# Covox_backplate.net
KiCad netlist of a schematic drawn in EasyEDA
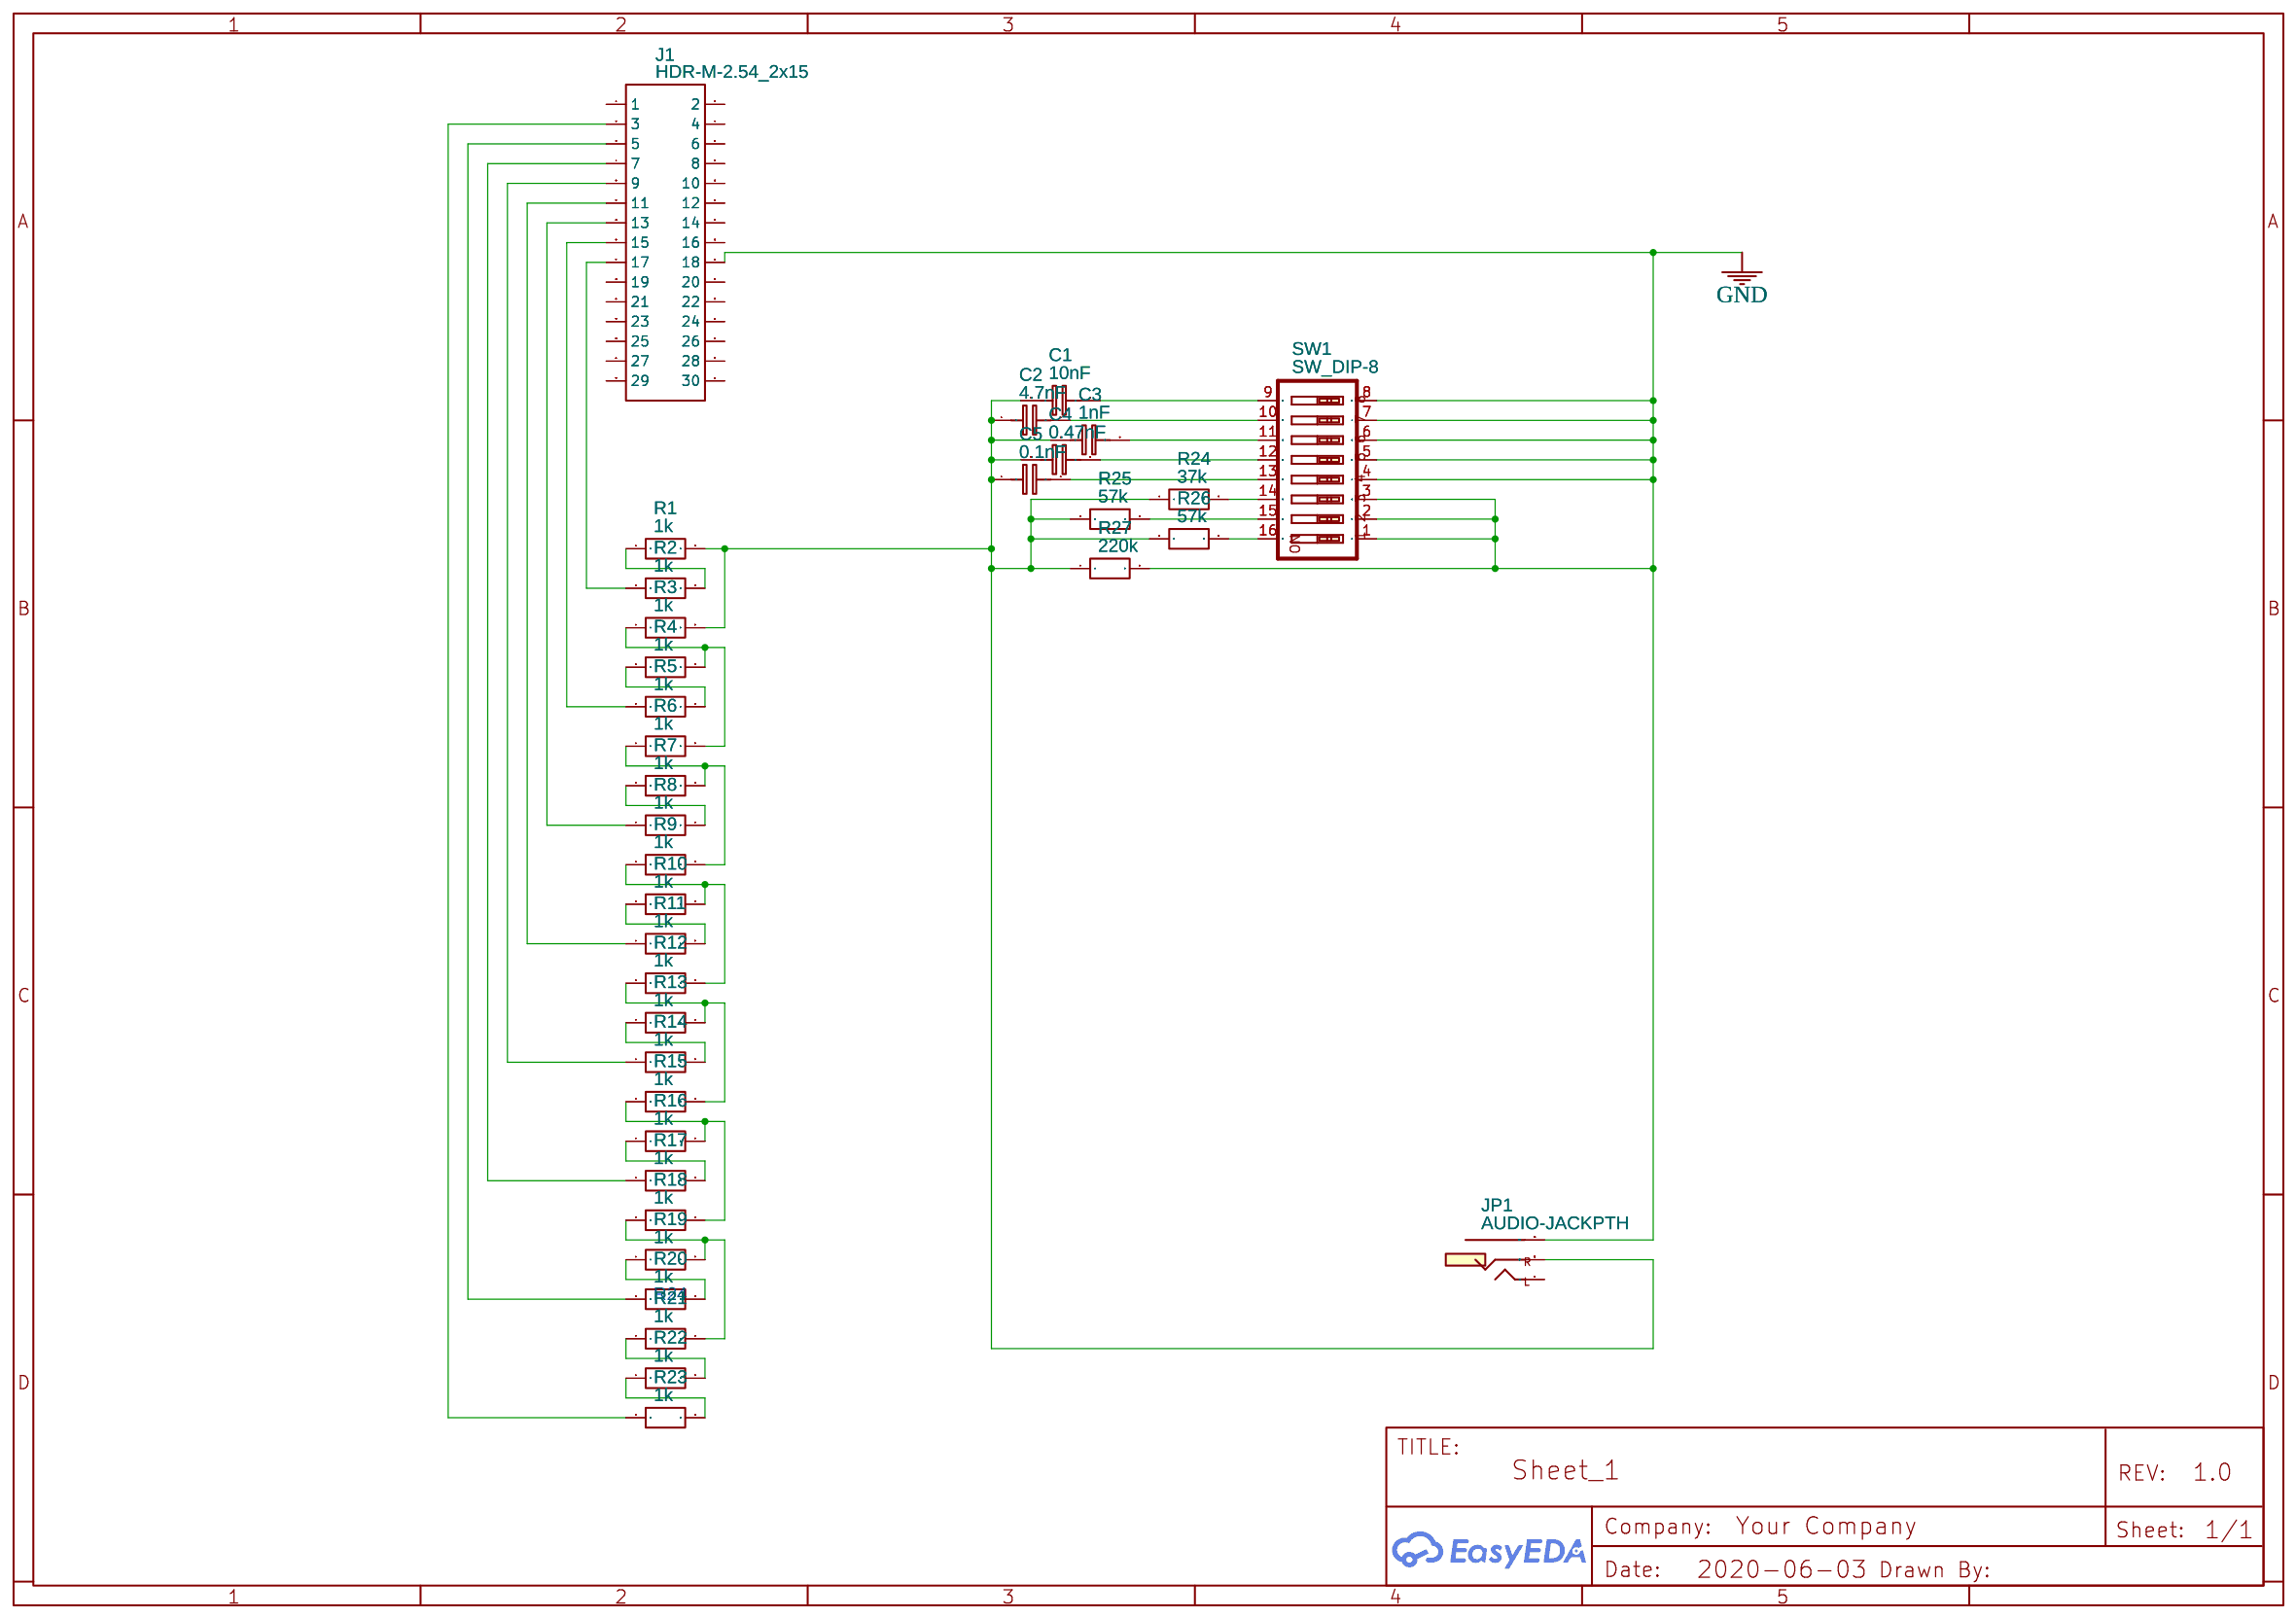
[diagram p0: schematic sheet]

(export (version "E")
  (design (tool "Eeschema 10.0.6"))
  (components
    (comp (ref "C1") (value "10nF") (libsource (lib "") (part "C_0201_EU")))
    (comp (ref "C2") (value "4.7nF") (libsource (lib "") (part "C_0201_EU")))
    (comp (ref "C3") (value "1nF") (libsource (lib "") (part "C_0201_EU")))
    (comp (ref "C4") (value "0.47nF") (libsource (lib "") (part "C_0201_EU")))
    (comp (ref "C5") (value "0.1nF") (libsource (lib "") (part "C_0201_EU")))
    (comp (ref "J1")
      (value "HDR-M-2.54_2x15")
      (fields (field (name "BOM_Supplier Part") "C56496"))
      (libsource (lib "") (part "HDR-M-2.54_2x15"))
    )
    (comp (ref "JP1") (value "AUDIO-JACKPTH") (libsource (lib "") (part "AUDIO-JACKPTH")))
    (comp (ref "R1") (value "1k") (libsource (lib "") (part "R_0201_EU")))
    (comp (ref "R2") (value "1k") (libsource (lib "") (part "R_0201_EU")))
    (comp (ref "R3") (value "1k") (libsource (lib "") (part "R_0201_EU")))
    (comp (ref "R4") (value "1k") (libsource (lib "") (part "R_0201_EU")))
    (comp (ref "R5") (value "1k") (libsource (lib "") (part "R_0201_EU")))
    (comp (ref "R6") (value "1k") (libsource (lib "") (part "R_0201_EU")))
    (comp (ref "R7") (value "1k") (libsource (lib "") (part "R_0201_EU")))
    (comp (ref "R8") (value "1k") (libsource (lib "") (part "R_0201_EU")))
    (comp (ref "R9") (value "1k") (libsource (lib "") (part "R_0201_EU")))
    (comp (ref "R10") (value "1k") (libsource (lib "") (part "R_0201_EU")))
    (comp (ref "R11") (value "1k") (libsource (lib "") (part "R_0201_EU")))
    (comp (ref "R12") (value "1k") (libsource (lib "") (part "R_0201_EU")))
    (comp (ref "R13") (value "1k") (libsource (lib "") (part "R_0201_EU")))
    (comp (ref "R14") (value "1k") (libsource (lib "") (part "R_0201_EU")))
    (comp (ref "R15") (value "1k") (libsource (lib "") (part "R_0201_EU")))
    (comp (ref "R16") (value "1k") (libsource (lib "") (part "R_0201_EU")))
    (comp (ref "R17") (value "1k") (libsource (lib "") (part "R_0201_EU")))
    (comp (ref "R18") (value "1k") (libsource (lib "") (part "R_0201_EU")))
    (comp (ref "R19") (value "1k") (libsource (lib "") (part "R_0201_EU")))
    (comp (ref "R20") (value "1k") (libsource (lib "") (part "R_0201_EU")))
    (comp (ref "R21") (value "1k") (libsource (lib "") (part "R_0201_EU")))
    (comp (ref "R22") (value "1k") (libsource (lib "") (part "R_0201_EU")))
    (comp (ref "R23") (value "1k") (libsource (lib "") (part "R_0201_EU")))
    (comp (ref "R24") (value "37k") (libsource (lib "") (part "R_0201_EU")))
    (comp (ref "R25") (value "57k") (libsource (lib "") (part "R_0201_EU")))
    (comp (ref "R26") (value "57k") (libsource (lib "") (part "R_0201_EU")))
    (comp (ref "R27") (value "220k") (libsource (lib "") (part "R_0201_EU")))
    (comp (ref "SW1") (value "SW_DIP-8") (libsource (lib "") (part "SW_DIP-8")))
  )
  (nets
    (net (code "1") (name "GND") (class "Default")
      (node (ref "J1") (pin "18") (pinfunction "18_18") (pintype "input"))
      (node (ref "JP1") (pin "SLEEVE") (pinfunction "SLEEVE_SLEEVE") (pintype "unspecified"))
      (node (ref "R27") (pin "2") (pinfunction "2_2") (pintype "unspecified"))
      (node (ref "SW1") (pin "1") (pinfunction "1_1") (pintype "unspecified"))
      (node (ref "SW1") (pin "2") (pinfunction "2_2") (pintype "unspecified"))
      (node (ref "SW1") (pin "3") (pinfunction "3_3") (pintype "unspecified"))
      (node (ref "SW1") (pin "4") (pinfunction "4_4") (pintype "unspecified"))
      (node (ref "SW1") (pin "5") (pinfunction "5_5") (pintype "unspecified"))
      (node (ref "SW1") (pin "6") (pinfunction "6_6") (pintype "unspecified"))
      (node (ref "SW1") (pin "7") (pinfunction "7_7") (pintype "unspecified"))
      (node (ref "SW1") (pin "8") (pinfunction "8_8") (pintype "unspecified"))
    )
    (net (code "2") (name "Net-(C1-Pad2)") (class "Default")
      (node (ref "C1") (pin "2") (pinfunction "2_2") (pintype "unspecified"))
      (node (ref "SW1") (pin "9") (pinfunction "9_9") (pintype "unspecified"))
    )
    (net (code "3") (name "Net-(C2-Pad2)") (class "Default")
      (node (ref "C2") (pin "2") (pinfunction "2_2") (pintype "unspecified"))
      (node (ref "SW1") (pin "10") (pinfunction "10_10") (pintype "unspecified"))
    )
    (net (code "4") (name "Net-(C3-Pad2)") (class "Default")
      (node (ref "C3") (pin "2") (pinfunction "2_2") (pintype "unspecified"))
      (node (ref "SW1") (pin "11") (pinfunction "11_11") (pintype "unspecified"))
    )
    (net (code "5") (name "Net-(C4-Pad2)") (class "Default")
      (node (ref "C4") (pin "2") (pinfunction "2_2") (pintype "unspecified"))
      (node (ref "SW1") (pin "12") (pinfunction "12_12") (pintype "unspecified"))
    )
    (net (code "6") (name "Net-(C5-Pad2)") (class "Default")
      (node (ref "C5") (pin "2") (pinfunction "2_2") (pintype "unspecified"))
      (node (ref "SW1") (pin "13") (pinfunction "13_13") (pintype "unspecified"))
    )
    (net (code "7") (name "Net-(J1-Pad3)") (class "Default")
      (node (ref "J1") (pin "3") (pinfunction "3_3") (pintype "input"))
      (node (ref "R23") (pin "1") (pinfunction "1_1") (pintype "unspecified"))
    )
    (net (code "8") (name "Net-(J1-Pad5)") (class "Default")
      (node (ref "J1") (pin "5") (pinfunction "5_5") (pintype "input"))
      (node (ref "R20") (pin "1") (pinfunction "1_1") (pintype "unspecified"))
    )
    (net (code "9") (name "Net-(J1-Pad7)") (class "Default")
      (node (ref "J1") (pin "7") (pinfunction "7_7") (pintype "input"))
      (node (ref "R17") (pin "1") (pinfunction "1_1") (pintype "unspecified"))
    )
    (net (code "10") (name "Net-(J1-Pad9)") (class "Default")
      (node (ref "J1") (pin "9") (pinfunction "9_9") (pintype "input"))
      (node (ref "R14") (pin "1") (pinfunction "1_1") (pintype "unspecified"))
    )
    (net (code "11") (name "Net-(J1-Pad11)") (class "Default")
      (node (ref "J1") (pin "11") (pinfunction "11_11") (pintype "input"))
      (node (ref "R11") (pin "1") (pinfunction "1_1") (pintype "unspecified"))
    )
    (net (code "12") (name "Net-(J1-Pad13)") (class "Default")
      (node (ref "J1") (pin "13") (pinfunction "13_13") (pintype "input"))
      (node (ref "R8") (pin "1") (pinfunction "1_1") (pintype "unspecified"))
    )
    (net (code "13") (name "Net-(J1-Pad15)") (class "Default")
      (node (ref "J1") (pin "15") (pinfunction "15_15") (pintype "input"))
      (node (ref "R5") (pin "1") (pinfunction "1_1") (pintype "unspecified"))
    )
    (net (code "14") (name "Net-(J1-Pad17)") (class "Default")
      (node (ref "J1") (pin "17") (pinfunction "17_17") (pintype "input"))
      (node (ref "R2") (pin "1") (pinfunction "1_1") (pintype "unspecified"))
    )
    (net (code "15") (name "Net-(JP1-RIGHT)") (class "Default")
      (node (ref "C1") (pin "1") (pinfunction "1_1") (pintype "unspecified"))
      (node (ref "C2") (pin "1") (pinfunction "1_1") (pintype "unspecified"))
      (node (ref "C3") (pin "1") (pinfunction "1_1") (pintype "unspecified"))
      (node (ref "C4") (pin "1") (pinfunction "1_1") (pintype "unspecified"))
      (node (ref "C5") (pin "1") (pinfunction "1_1") (pintype "unspecified"))
      (node (ref "JP1") (pin "RING") (pinfunction "RIGHT_RING") (pintype "unspecified"))
      (node (ref "R1") (pin "2") (pinfunction "2_2") (pintype "unspecified"))
      (node (ref "R24") (pin "1") (pinfunction "1_1") (pintype "unspecified"))
      (node (ref "R25") (pin "1") (pinfunction "1_1") (pintype "unspecified"))
      (node (ref "R26") (pin "1") (pinfunction "1_1") (pintype "unspecified"))
      (node (ref "R27") (pin "1") (pinfunction "1_1") (pintype "unspecified"))
      (node (ref "R3") (pin "2") (pinfunction "2_2") (pintype "unspecified"))
    )
    (net (code "16") (name "Net-(R1-Pad1)") (class "Default")
      (node (ref "R1") (pin "1") (pinfunction "1_1") (pintype "unspecified"))
      (node (ref "R2") (pin "2") (pinfunction "2_2") (pintype "unspecified"))
    )
    (net (code "17") (name "Net-(R3-Pad1)") (class "Default")
      (node (ref "R3") (pin "1") (pinfunction "1_1") (pintype "unspecified"))
      (node (ref "R4") (pin "2") (pinfunction "2_2") (pintype "unspecified"))
      (node (ref "R6") (pin "2") (pinfunction "2_2") (pintype "unspecified"))
    )
    (net (code "18") (name "Net-(R4-Pad1)") (class "Default")
      (node (ref "R4") (pin "1") (pinfunction "1_1") (pintype "unspecified"))
      (node (ref "R5") (pin "2") (pinfunction "2_2") (pintype "unspecified"))
    )
    (net (code "19") (name "Net-(R6-Pad1)") (class "Default")
      (node (ref "R6") (pin "1") (pinfunction "1_1") (pintype "unspecified"))
      (node (ref "R7") (pin "2") (pinfunction "2_2") (pintype "unspecified"))
      (node (ref "R9") (pin "2") (pinfunction "2_2") (pintype "unspecified"))
    )
    (net (code "20") (name "Net-(R7-Pad1)") (class "Default")
      (node (ref "R7") (pin "1") (pinfunction "1_1") (pintype "unspecified"))
      (node (ref "R8") (pin "2") (pinfunction "2_2") (pintype "unspecified"))
    )
    (net (code "21") (name "Net-(R10-Pad1)") (class "Default")
      (node (ref "R10") (pin "1") (pinfunction "1_1") (pintype "unspecified"))
      (node (ref "R11") (pin "2") (pinfunction "2_2") (pintype "unspecified"))
    )
    (net (code "22") (name "Net-(R10-Pad2)") (class "Default")
      (node (ref "R10") (pin "2") (pinfunction "2_2") (pintype "unspecified"))
      (node (ref "R12") (pin "2") (pinfunction "2_2") (pintype "unspecified"))
      (node (ref "R9") (pin "1") (pinfunction "1_1") (pintype "unspecified"))
    )
    (net (code "23") (name "Net-(R12-Pad1)") (class "Default")
      (node (ref "R12") (pin "1") (pinfunction "1_1") (pintype "unspecified"))
      (node (ref "R13") (pin "2") (pinfunction "2_2") (pintype "unspecified"))
      (node (ref "R15") (pin "2") (pinfunction "2_2") (pintype "unspecified"))
    )
    (net (code "24") (name "Net-(R13-Pad1)") (class "Default")
      (node (ref "R13") (pin "1") (pinfunction "1_1") (pintype "unspecified"))
      (node (ref "R14") (pin "2") (pinfunction "2_2") (pintype "unspecified"))
    )
    (net (code "25") (name "Net-(R15-Pad1)") (class "Default")
      (node (ref "R15") (pin "1") (pinfunction "1_1") (pintype "unspecified"))
      (node (ref "R16") (pin "2") (pinfunction "2_2") (pintype "unspecified"))
      (node (ref "R18") (pin "2") (pinfunction "2_2") (pintype "unspecified"))
    )
    (net (code "26") (name "Net-(R16-Pad1)") (class "Default")
      (node (ref "R16") (pin "1") (pinfunction "1_1") (pintype "unspecified"))
      (node (ref "R17") (pin "2") (pinfunction "2_2") (pintype "unspecified"))
    )
    (net (code "27") (name "Net-(R18-Pad1)") (class "Default")
      (node (ref "R18") (pin "1") (pinfunction "1_1") (pintype "unspecified"))
      (node (ref "R19") (pin "2") (pinfunction "2_2") (pintype "unspecified"))
      (node (ref "R21") (pin "2") (pinfunction "2_2") (pintype "unspecified"))
    )
    (net (code "28") (name "Net-(R19-Pad1)") (class "Default")
      (node (ref "R19") (pin "1") (pinfunction "1_1") (pintype "unspecified"))
      (node (ref "R20") (pin "2") (pinfunction "2_2") (pintype "unspecified"))
    )
    (net (code "29") (name "Net-(R21-Pad1)") (class "Default")
      (node (ref "R21") (pin "1") (pinfunction "1_1") (pintype "unspecified"))
      (node (ref "R22") (pin "2") (pinfunction "2_2") (pintype "unspecified"))
    )
    (net (code "30") (name "Net-(R22-Pad1)") (class "Default")
      (node (ref "R22") (pin "1") (pinfunction "1_1") (pintype "unspecified"))
      (node (ref "R23") (pin "2") (pinfunction "2_2") (pintype "unspecified"))
    )
    (net (code "31") (name "Net-(R24-Pad2)") (class "Default")
      (node (ref "R24") (pin "2") (pinfunction "2_2") (pintype "unspecified"))
      (node (ref "SW1") (pin "14") (pinfunction "14_14") (pintype "unspecified"))
    )
    (net (code "32") (name "Net-(R25-Pad2)") (class "Default")
      (node (ref "R25") (pin "2") (pinfunction "2_2") (pintype "unspecified"))
      (node (ref "SW1") (pin "15") (pinfunction "15_15") (pintype "unspecified"))
    )
    (net (code "33") (name "Net-(R26-Pad2)") (class "Default")
      (node (ref "R26") (pin "2") (pinfunction "2_2") (pintype "unspecified"))
      (node (ref "SW1") (pin "16") (pinfunction "16_16") (pintype "unspecified"))
    )
    (net (code "34") (name "unconnected-(J1-Pad1)") (class "Default")
      (node (ref "J1") (pin "1") (pinfunction "1_1") (pintype "input"))
    )
    (net (code "35") (name "unconnected-(J1-Pad2)") (class "Default")
      (node (ref "J1") (pin "2") (pinfunction "2_2") (pintype "input"))
    )
    (net (code "36") (name "unconnected-(J1-Pad4)") (class "Default")
      (node (ref "J1") (pin "4") (pinfunction "4_4") (pintype "input"))
    )
    (net (code "37") (name "unconnected-(J1-Pad6)") (class "Default")
      (node (ref "J1") (pin "6") (pinfunction "6_6") (pintype "input"))
    )
    (net (code "38") (name "unconnected-(J1-Pad8)") (class "Default")
      (node (ref "J1") (pin "8") (pinfunction "8_8") (pintype "input"))
    )
    (net (code "39") (name "unconnected-(J1-Pad10)") (class "Default")
      (node (ref "J1") (pin "10") (pinfunction "10_10") (pintype "input"))
    )
    (net (code "40") (name "unconnected-(J1-Pad12)") (class "Default")
      (node (ref "J1") (pin "12") (pinfunction "12_12") (pintype "input"))
    )
    (net (code "41") (name "unconnected-(J1-Pad14)") (class "Default")
      (node (ref "J1") (pin "14") (pinfunction "14_14") (pintype "input"))
    )
    (net (code "42") (name "unconnected-(J1-Pad16)") (class "Default")
      (node (ref "J1") (pin "16") (pinfunction "16_16") (pintype "input"))
    )
    (net (code "43") (name "unconnected-(J1-Pad19)") (class "Default")
      (node (ref "J1") (pin "19") (pinfunction "19_19") (pintype "input"))
    )
    (net (code "44") (name "unconnected-(J1-Pad20)") (class "Default")
      (node (ref "J1") (pin "20") (pinfunction "20_20") (pintype "input"))
    )
    (net (code "45") (name "unconnected-(J1-Pad21)") (class "Default")
      (node (ref "J1") (pin "21") (pinfunction "21_21") (pintype "input"))
    )
    (net (code "46") (name "unconnected-(J1-Pad22)") (class "Default")
      (node (ref "J1") (pin "22") (pinfunction "22_22") (pintype "input"))
    )
    (net (code "47") (name "unconnected-(J1-Pad23)") (class "Default")
      (node (ref "J1") (pin "23") (pinfunction "23_23") (pintype "input"))
    )
    (net (code "48") (name "unconnected-(J1-Pad24)") (class "Default")
      (node (ref "J1") (pin "24") (pinfunction "24_24") (pintype "input"))
    )
    (net (code "49") (name "unconnected-(J1-Pad25)") (class "Default")
      (node (ref "J1") (pin "25") (pinfunction "25_25") (pintype "input"))
    )
    (net (code "50") (name "unconnected-(J1-Pad26)") (class "Default")
      (node (ref "J1") (pin "26") (pinfunction "26_26") (pintype "input"))
    )
    (net (code "51") (name "unconnected-(J1-Pad27)") (class "Default")
      (node (ref "J1") (pin "27") (pinfunction "27_27") (pintype "input"))
    )
    (net (code "52") (name "unconnected-(J1-Pad28)") (class "Default")
      (node (ref "J1") (pin "28") (pinfunction "28_28") (pintype "input"))
    )
    (net (code "53") (name "unconnected-(J1-Pad29)") (class "Default")
      (node (ref "J1") (pin "29") (pinfunction "29_29") (pintype "input"))
    )
    (net (code "54") (name "unconnected-(J1-Pad30)") (class "Default")
      (node (ref "J1") (pin "30") (pinfunction "30_30") (pintype "input"))
    )
    (net (code "55") (name "unconnected-(JP1-LEFT-PadTIP)") (class "Default")
      (node (ref "JP1") (pin "TIP") (pinfunction "LEFT_TIP") (pintype "unspecified"))
    )
  )
)
